# Bi_Dir_Circuit.net
KiCad netlist of a schematic drawn in Altium Designer
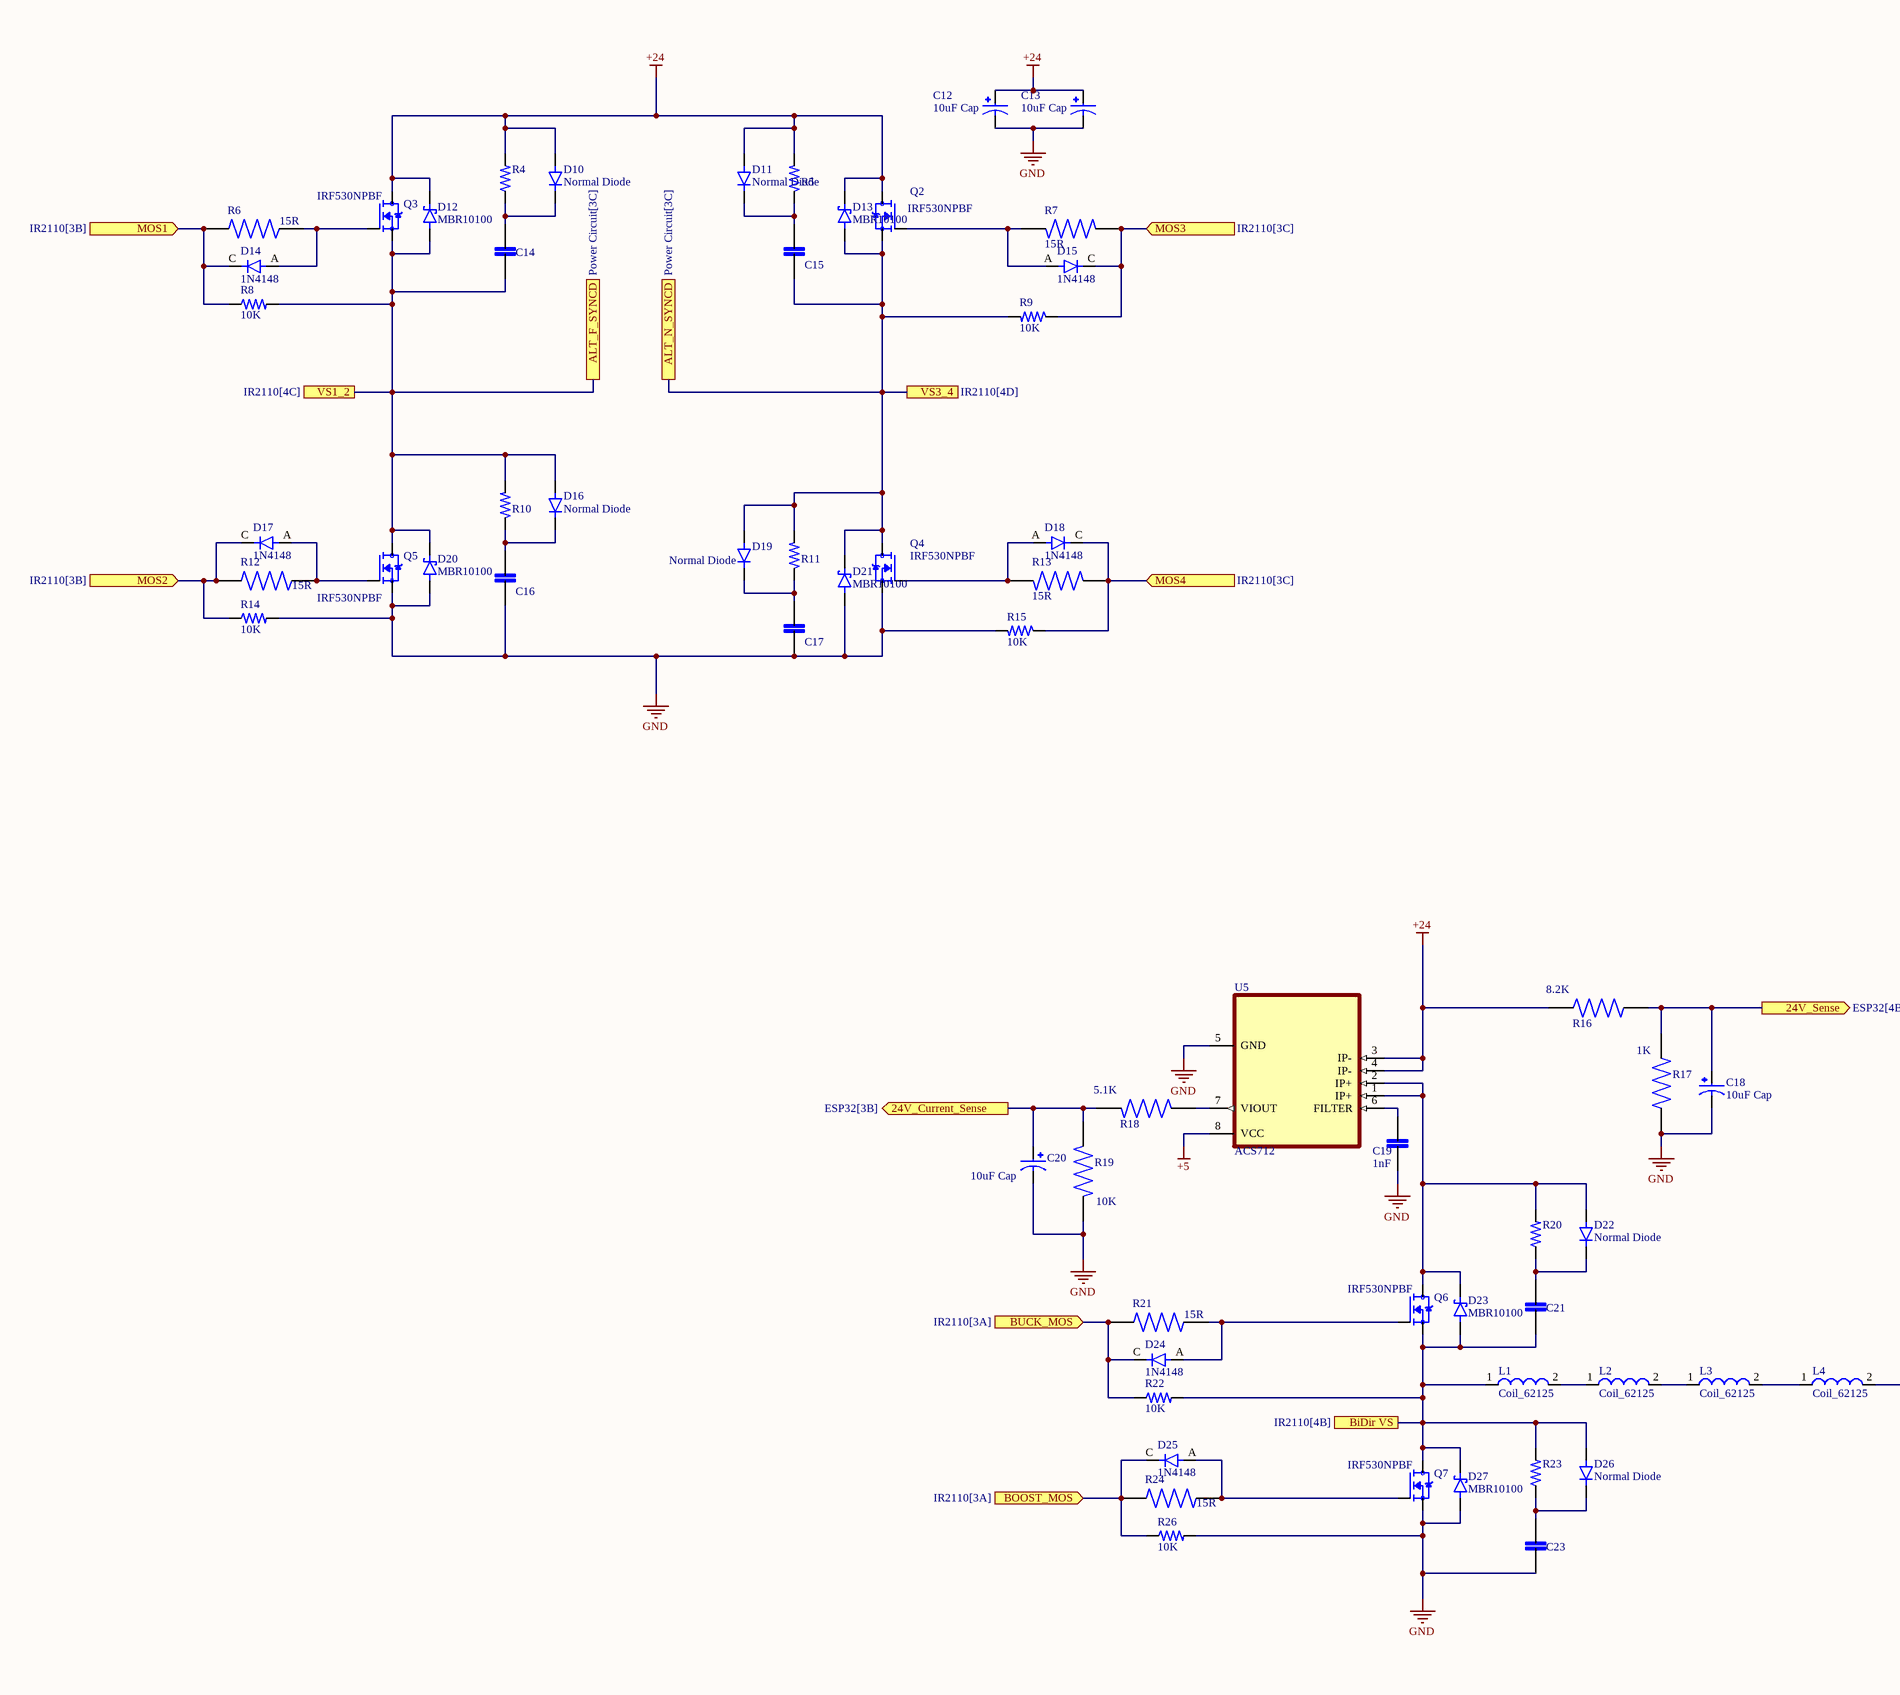
[diagram p0: Bi_Dir_Circuit.SchDoc, left]
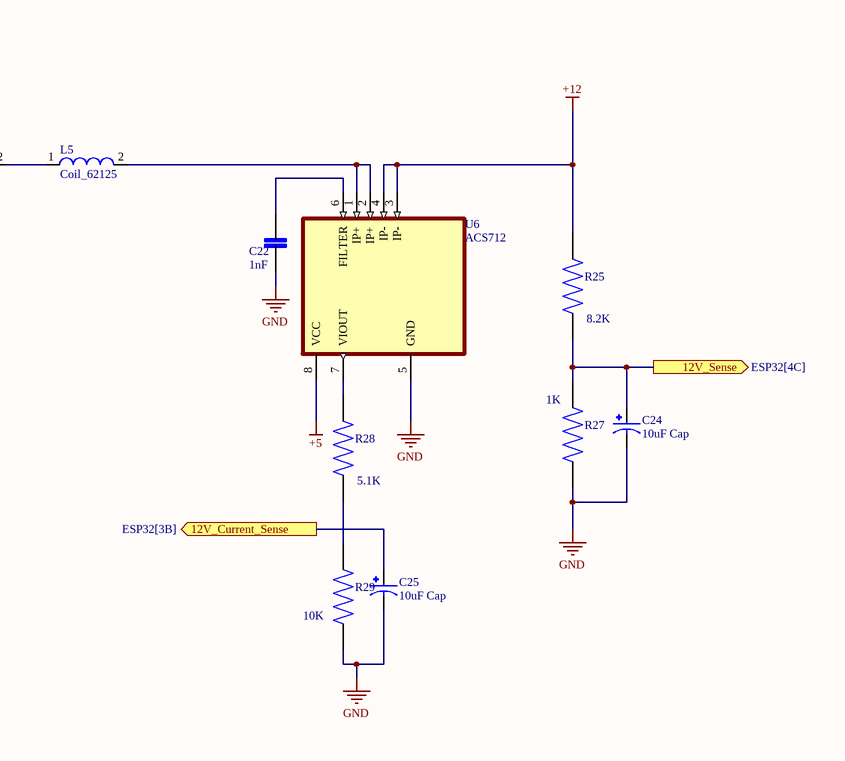
[diagram p1: Bi_Dir_Circuit.SchDoc, right]

(export (version "E")
  (design (tool "Eeschema 10.0.6"))
  (components
    (comp (ref "C12")
      (value "10uF Cap")
      (footprint "2200uF_Cap")
      (description "CAP ALUM 10UF 20% 50V RADIAL")
      (fields (field (name "MP") "ECE-A1HN100UI") (field (name "MF") "Panasonic"))
      (libsource (lib "MySCH_Library") (part "10uF Cap"))
    )
    (comp (ref "C13")
      (value "10uF Cap")
      (footprint "2200uF_Cap")
      (description "CAP ALUM 10UF 20% 50V RADIAL")
      (fields (field (name "MP") "ECE-A1HN100UI") (field (name "MF") "Panasonic"))
      (libsource (lib "MySCH_Library") (part "10uF Cap"))
    )
    (comp (ref "C14")
      (value "Ceramic Capacitor")
      (footprint "Ceramic Capacitor")
      (fields (field (name "MP") "LD051A121KAB2A") (field (name "MF") "AVX"))
      (libsource (lib "") (part "Ceramic Capacitor_1"))
    )
    (comp (ref "C15")
      (value "Ceramic Capacitor")
      (footprint "Ceramic Capacitor")
      (fields (field (name "MP") "LD051A121KAB2A") (field (name "MF") "AVX"))
      (libsource (lib "Capacitors Through Hole") (part "Ceramic Capacitor"))
    )
    (comp (ref "C16")
      (value "Ceramic Capacitor")
      (footprint "Ceramic Capacitor")
      (fields (field (name "MP") "LD051A121KAB2A") (field (name "MF") "AVX"))
      (libsource (lib "Capacitors Through Hole") (part "Ceramic Capacitor"))
    )
    (comp (ref "C17")
      (value "Ceramic Capacitor")
      (footprint "Ceramic Capacitor")
      (fields (field (name "MP") "LD051A121KAB2A") (field (name "MF") "AVX"))
      (libsource (lib "Capacitors Through Hole") (part "Ceramic Capacitor"))
    )
    (comp (ref "C18")
      (value "10uF Cap")
      (footprint "CAP_10uF")
      (description "CAP ALUM 10UF 20% 50V RADIAL")
      (fields (field (name "MP") "ECE-A1HN100UI") (field (name "MF") "Panasonic"))
      (libsource (lib "MySCH_Library") (part "10uF Cap"))
    )
    (comp (ref "C19")
      (value "1nF")
      (footprint "Ceramic Capacitor")
      (fields (field (name "MP") "LD051A121KAB2A") (field (name "MF") "AVX"))
      (libsource (lib "") (part "Ceramic Capacitor_1"))
    )
    (comp (ref "C20")
      (value "10uF Cap")
      (footprint "CAP_10uF")
      (description "CAP ALUM 10UF 20% 50V RADIAL")
      (fields (field (name "MP") "ECE-A1HN100UI") (field (name "MF") "Panasonic"))
      (libsource (lib "") (part "10uF Cap_1"))
    )
    (comp (ref "C21")
      (value "Ceramic Capacitor")
      (footprint "Ceramic Capacitor")
      (fields (field (name "MP") "LD051A121KAB2A") (field (name "MF") "AVX"))
      (libsource (lib "") (part "Ceramic Capacitor_1"))
    )
    (comp (ref "C22")
      (value "1nF")
      (footprint "Ceramic Capacitor")
      (fields (field (name "MP") "LD051A121KAB2A") (field (name "MF") "AVX"))
      (libsource (lib "") (part "Ceramic Capacitor_1"))
    )
    (comp (ref "C23")
      (value "Ceramic Capacitor")
      (footprint "Ceramic Capacitor")
      (fields (field (name "MP") "LD051A121KAB2A") (field (name "MF") "AVX"))
      (libsource (lib "") (part "Ceramic Capacitor_1"))
    )
    (comp (ref "C24")
      (value "10uF Cap")
      (footprint "CAP_10uF")
      (description "CAP ALUM 10UF 20% 50V RADIAL")
      (fields (field (name "MP") "ECE-A1HN100UI") (field (name "MF") "Panasonic"))
      (libsource (lib "MySCH_Library") (part "10uF Cap"))
    )
    (comp (ref "C25")
      (value "10uF Cap")
      (footprint "CAP_10uF")
      (description "CAP ALUM 10UF 20% 50V RADIAL")
      (fields (field (name "MP") "ECE-A1HN100UI") (field (name "MF") "Panasonic"))
      (libsource (lib "MySCH_Library") (part "10uF Cap"))
    )
    (comp (ref "D10")
      (value "Normal Diode")
      (footprint "Common Trhough Hole")
      (fields (field (name "MF") "NTE Electronics, Inc.") (field (name "MP") "1N4007"))
      (libsource (lib "Diodes Through Hole") (part "Normal Diode"))
    )
    (comp (ref "D11")
      (value "Normal Diode")
      (footprint "Common Trhough Hole")
      (fields (field (name "MF") "NTE Electronics, Inc.") (field (name "MP") "1N4007"))
      (libsource (lib "Diodes Through Hole") (part "Normal Diode"))
    )
    (comp (ref "D12")
      (value "MBR10100")
      (footprint "MBR10100")
      (fields (field (name "MF") "Diodes Inc.") (field (name "MP") "1N5817-T"))
      (libsource (lib "Diodes Through Hole") (part "MBR10100"))
    )
    (comp (ref "D13")
      (value "MBR10100")
      (footprint "MBR10100")
      (fields (field (name "MF") "Diodes Inc.") (field (name "MP") "1N5817-T"))
      (libsource (lib "Diodes Through Hole") (part "MBR10100"))
    )
    (comp (ref "D14")
      (value "1N4148")
      (footprint "1N4007 DIODE")
      (description "Diode Standard 1000 V 1A Through Hole DO-41")
      (fields (field (name "MF") "NTE Electronics, Inc.") (field (name "MP") "1N4007"))
      (libsource (lib "MySCH_Library") (part "1N4007"))
    )
    (comp (ref "D15")
      (value "1N4148")
      (footprint "1N4007 DIODE")
      (description "Diode Standard 1000 V 1A Through Hole DO-41")
      (fields (field (name "MF") "NTE Electronics, Inc.") (field (name "MP") "1N4007"))
      (libsource (lib "MySCH_Library") (part "1N4007"))
    )
    (comp (ref "D16")
      (value "Normal Diode")
      (footprint "Common Trhough Hole")
      (fields (field (name "MF") "NTE Electronics, Inc.") (field (name "MP") "1N4007"))
      (libsource (lib "Diodes Through Hole") (part "Normal Diode"))
    )
    (comp (ref "D17")
      (value "1N4148")
      (footprint "1N4007 DIODE")
      (description "Diode Standard 1000 V 1A Through Hole DO-41")
      (fields (field (name "MF") "NTE Electronics, Inc.") (field (name "MP") "1N4007"))
      (libsource (lib "MySCH_Library") (part "1N4007"))
    )
    (comp (ref "D18")
      (value "1N4148")
      (footprint "1N4007 DIODE")
      (description "Diode Standard 1000 V 1A Through Hole DO-41")
      (fields (field (name "MF") "NTE Electronics, Inc.") (field (name "MP") "1N4007"))
      (libsource (lib "MySCH_Library") (part "1N4007"))
    )
    (comp (ref "D19")
      (value "Normal Diode")
      (footprint "Common Trhough Hole")
      (fields (field (name "MF") "NTE Electronics, Inc.") (field (name "MP") "1N4007"))
      (libsource (lib "Diodes Through Hole") (part "Normal Diode"))
    )
    (comp (ref "D20")
      (value "MBR10100")
      (footprint "MBR10100")
      (fields (field (name "MF") "Diodes Inc.") (field (name "MP") "1N5817-T"))
      (libsource (lib "Diodes Through Hole") (part "MBR10100"))
    )
    (comp (ref "D21")
      (value "MBR10100")
      (footprint "MBR10100")
      (fields (field (name "MF") "Diodes Inc.") (field (name "MP") "1N5817-T"))
      (libsource (lib "Diodes Through Hole") (part "MBR10100"))
    )
    (comp (ref "D22")
      (value "Normal Diode")
      (footprint "Common Trhough Hole")
      (fields (field (name "MF") "NTE Electronics, Inc.") (field (name "MP") "1N4007"))
      (libsource (lib "Diodes Through Hole") (part "Normal Diode"))
    )
    (comp (ref "D23")
      (value "MBR10100")
      (footprint "MBR10100")
      (fields (field (name "MF") "Diodes Inc.") (field (name "MP") "1N5817-T"))
      (libsource (lib "Diodes Through Hole") (part "MBR10100"))
    )
    (comp (ref "D24")
      (value "1N4148")
      (footprint "1N4007 DIODE")
      (description "Diode Standard 1000 V 1A Through Hole DO-41")
      (fields (field (name "MF") "NTE Electronics, Inc.") (field (name "MP") "1N4007"))
      (libsource (lib "MySCH_Library") (part "1N4007"))
    )
    (comp (ref "D25")
      (value "1N4148")
      (footprint "1N4007 DIODE")
      (description "Diode Standard 1000 V 1A Through Hole DO-41")
      (fields (field (name "MF") "NTE Electronics, Inc.") (field (name "MP") "1N4007"))
      (libsource (lib "MySCH_Library") (part "1N4007"))
    )
    (comp (ref "D26")
      (value "Normal Diode")
      (footprint "Common Trhough Hole")
      (fields (field (name "MF") "NTE Electronics, Inc.") (field (name "MP") "1N4007"))
      (libsource (lib "Diodes Through Hole") (part "Normal Diode"))
    )
    (comp (ref "D27")
      (value "MBR10100")
      (footprint "MBR10100")
      (fields (field (name "MF") "Diodes Inc.") (field (name "MP") "1N5817-T"))
      (libsource (lib "Diodes Through Hole") (part "MBR10100"))
    )
    (comp (ref "L1")
      (value "Coil_62125")
      (footprint "Coil 65125")
      (description "Inductor Power Wirewound 470uH 10% 1KHz 25Q-Factor Ferrite 210mA 3.3Ohm DCR T/R")
      (fields (field (name "DIGI-KEY_PART_NUMBER") "SDR0604-471KLCT-ND") (field (name "MF") "Bourns"))
      (libsource (lib "MySCH_Library") (part "Coil_62125"))
    )
    (comp (ref "L2")
      (value "Coil_62125")
      (footprint "Coil 65125")
      (description "Inductor Power Wirewound 470uH 10% 1KHz 25Q-Factor Ferrite 210mA 3.3Ohm DCR T/R")
      (fields (field (name "DIGI-KEY_PART_NUMBER") "SDR0604-471KLCT-ND") (field (name "MF") "Bourns"))
      (libsource (lib "MySCH_Library") (part "Coil_62125"))
    )
    (comp (ref "L3")
      (value "Coil_62125")
      (footprint "Coil 65125")
      (description "Inductor Power Wirewound 470uH 10% 1KHz 25Q-Factor Ferrite 210mA 3.3Ohm DCR T/R")
      (fields (field (name "DIGI-KEY_PART_NUMBER") "SDR0604-471KLCT-ND") (field (name "MF") "Bourns"))
      (libsource (lib "MySCH_Library") (part "Coil_62125"))
    )
    (comp (ref "L4")
      (value "Coil_62125")
      (footprint "Coil 65125")
      (description "Inductor Power Wirewound 470uH 10% 1KHz 25Q-Factor Ferrite 210mA 3.3Ohm DCR T/R")
      (fields (field (name "DIGI-KEY_PART_NUMBER") "SDR0604-471KLCT-ND") (field (name "MF") "Bourns"))
      (libsource (lib "MySCH_Library") (part "Coil_62125"))
    )
    (comp (ref "L5")
      (value "Coil_62125")
      (footprint "Coil 65125")
      (description "Inductor Power Wirewound 470uH 10% 1KHz 25Q-Factor Ferrite 210mA 3.3Ohm DCR T/R")
      (fields (field (name "DIGI-KEY_PART_NUMBER") "SDR0604-471KLCT-ND") (field (name "MF") "Bourns"))
      (libsource (lib "MySCH_Library") (part "Coil_62125"))
    )
    (comp (ref "Q2")
      (value "IRF530NPBF")
      (footprint "IRF530N")
      (fields (field (name "MF") "Infineon Technologies"))
      (libsource (lib "MySCH_Library") (part "IRF530NPBF"))
    )
    (comp (ref "Q3")
      (value "IRF530NPBF")
      (footprint "IRF530N")
      (fields (field (name "MF") "Infineon Technologies"))
      (libsource (lib "MySCH_Library") (part "IRF530NPBF"))
    )
    (comp (ref "Q4")
      (value "IRF530NPBF")
      (footprint "IRF530N")
      (fields (field (name "MF") "Infineon Technologies"))
      (libsource (lib "MySCH_Library") (part "IRF530NPBF"))
    )
    (comp (ref "Q5")
      (value "IRF530NPBF")
      (footprint "IRF530N")
      (fields (field (name "MF") "Infineon Technologies"))
      (libsource (lib "MySCH_Library") (part "IRF530NPBF"))
    )
    (comp (ref "Q6")
      (value "IRF530NPBF")
      (footprint "IRF530N")
      (fields (field (name "MF") "Infineon Technologies"))
      (libsource (lib "MySCH_Library") (part "IRF530NPBF"))
    )
    (comp (ref "Q7")
      (value "IRF530NPBF")
      (footprint "IRF530N")
      (fields (field (name "MF") "Infineon Technologies"))
      (libsource (lib "MySCH_Library") (part "IRF530NPBF"))
    )
    (comp (ref "R4")
      (value "Resistor")
      (footprint "Resistor_Through Hole")
      (fields
        (field (name "MP") "2-2176053-0")
        (field (name "TOLERANCE") "1%")
        (field (name "MF") "TE Connectivity")
      )
      (libsource (lib "Resistors Through Hole") (part "Resistor"))
    )
    (comp (ref "R5")
      (value "Resistor")
      (footprint "Resistor_Through Hole")
      (fields
        (field (name "MP") "2-2176053-0")
        (field (name "TOLERANCE") "1%")
        (field (name "MF") "TE Connectivity")
      )
      (libsource (lib "Resistors Through Hole") (part "Resistor"))
    )
    (comp (ref "R6")
      (value "15R")
      (footprint "Resistor_Through Hole")
      (description "1.02 Ohms Â±1% 0.25W, 1/4W Through Hole Resistor Axial Metal Film")
      (fields (field (name "MP") "MFR-25FTE52-1R") (field (name "MF") "Yageo"))
      (libsource (lib "MySCH_Library") (part "Resistor_Through Hole"))
    )
    (comp (ref "R7")
      (value "15R")
      (footprint "Resistor_Through Hole")
      (description "1.02 Ohms Â±1% 0.25W, 1/4W Through Hole Resistor Axial Metal Film")
      (fields (field (name "MP") "MFR-25FTE52-1R") (field (name "MF") "Yageo"))
      (libsource (lib "MySCH_Library") (part "Resistor_Through Hole"))
    )
    (comp (ref "R8")
      (value "10K")
      (footprint "Resistor_Through Hole")
      (fields
        (field (name "MP") "2-2176053-0")
        (field (name "TOLERANCE") "1%")
        (field (name "MF") "TE Connectivity")
      )
      (libsource (lib "Resistors Through Hole") (part "Resistor"))
    )
    (comp (ref "R9")
      (value "10K")
      (footprint "Resistor_Through Hole")
      (fields
        (field (name "MP") "2-2176053-0")
        (field (name "TOLERANCE") "1%")
        (field (name "MF") "TE Connectivity")
      )
      (libsource (lib "Resistors Through Hole") (part "Resistor"))
    )
    (comp (ref "R10")
      (value "Resistor")
      (footprint "Resistor_Through Hole")
      (fields
        (field (name "MP") "2-2176053-0")
        (field (name "TOLERANCE") "1%")
        (field (name "MF") "TE Connectivity")
      )
      (libsource (lib "Resistors Through Hole") (part "Resistor"))
    )
    (comp (ref "R11")
      (value "Resistor")
      (footprint "Resistor_Through Hole")
      (fields
        (field (name "MP") "2-2176053-0")
        (field (name "TOLERANCE") "1%")
        (field (name "MF") "TE Connectivity")
      )
      (libsource (lib "Resistors Through Hole") (part "Resistor"))
    )
    (comp (ref "R12")
      (value "15R")
      (footprint "Resistor_Through Hole")
      (description "1.02 Ohms Â±1% 0.25W, 1/4W Through Hole Resistor Axial Metal Film")
      (fields (field (name "MP") "MFR-25FTE52-1R") (field (name "MF") "Yageo"))
      (libsource (lib "MySCH_Library") (part "Resistor_Through Hole"))
    )
    (comp (ref "R13")
      (value "15R")
      (footprint "Resistor_Through Hole")
      (description "1.02 Ohms Â±1% 0.25W, 1/4W Through Hole Resistor Axial Metal Film")
      (fields (field (name "MP") "MFR-25FTE52-1R") (field (name "MF") "Yageo"))
      (libsource (lib "MySCH_Library") (part "Resistor_Through Hole"))
    )
    (comp (ref "R14")
      (value "10K")
      (footprint "Resistor_Through Hole")
      (fields
        (field (name "MP") "2-2176053-0")
        (field (name "TOLERANCE") "1%")
        (field (name "MF") "TE Connectivity")
      )
      (libsource (lib "Resistors Through Hole") (part "Resistor"))
    )
    (comp (ref "R15")
      (value "10K")
      (footprint "Resistor_Through Hole")
      (fields
        (field (name "MP") "2-2176053-0")
        (field (name "TOLERANCE") "1%")
        (field (name "MF") "TE Connectivity")
      )
      (libsource (lib "Resistors Through Hole") (part "Resistor"))
    )
    (comp (ref "R16")
      (value "8.2K")
      (footprint "Resistor_Through Hole")
      (description "1.02 Ohms Â±1% 0.25W, 1/4W Through Hole Resistor Axial Metal Film")
      (fields (field (name "MP") "MFR-25FTE52-1R") (field (name "MF") "Yageo"))
      (libsource (lib "MySCH_Library") (part "Resistor_Through Hole"))
    )
    (comp (ref "R17")
      (value "1K")
      (footprint "Resistor_Through Hole")
      (description "1.02 Ohms Â±1% 0.25W, 1/4W Through Hole Resistor Axial Metal Film")
      (fields (field (name "MP") "MFR-25FTE52-1R") (field (name "MF") "Yageo"))
      (libsource (lib "MySCH_Library") (part "Resistor_Through Hole"))
    )
    (comp (ref "R18")
      (value "5.1K")
      (footprint "Resistor_Through Hole")
      (description "1.02 Ohms Â±1% 0.25W, 1/4W Through Hole Resistor Axial Metal Film")
      (fields (field (name "MP") "MFR-25FTE52-1R") (field (name "MF") "Yageo"))
      (libsource (lib "MySCH_Library") (part "Resistor_Through Hole"))
    )
    (comp (ref "R19")
      (value "10K")
      (footprint "Resistor_Through Hole")
      (description "1.02 Ohms Â±1% 0.25W, 1/4W Through Hole Resistor Axial Metal Film")
      (fields (field (name "MP") "MFR-25FTE52-1R") (field (name "MF") "Yageo"))
      (libsource (lib "MySCH_Library") (part "Resistor_Through Hole"))
    )
    (comp (ref "R20")
      (value "Resistor")
      (footprint "Resistor_Through Hole")
      (fields
        (field (name "MP") "2-2176053-0")
        (field (name "TOLERANCE") "1%")
        (field (name "MF") "TE Connectivity")
      )
      (libsource (lib "Resistors Through Hole") (part "Resistor"))
    )
    (comp (ref "R21")
      (value "15R")
      (footprint "Resistor_Through Hole")
      (description "1.02 Ohms Â±1% 0.25W, 1/4W Through Hole Resistor Axial Metal Film")
      (fields (field (name "MP") "MFR-25FTE52-1R") (field (name "MF") "Yageo"))
      (libsource (lib "MySCH_Library") (part "Resistor_Through Hole"))
    )
    (comp (ref "R22")
      (value "10K")
      (footprint "Resistor_Through Hole")
      (fields
        (field (name "MP") "2-2176053-0")
        (field (name "TOLERANCE") "1%")
        (field (name "MF") "TE Connectivity")
      )
      (libsource (lib "Resistors Through Hole") (part "Resistor"))
    )
    (comp (ref "R23")
      (value "Resistor")
      (footprint "Resistor_Through Hole")
      (fields
        (field (name "MP") "2-2176053-0")
        (field (name "TOLERANCE") "1%")
        (field (name "MF") "TE Connectivity")
      )
      (libsource (lib "Resistors Through Hole") (part "Resistor"))
    )
    (comp (ref "R24")
      (value "15R")
      (footprint "Resistor_Through Hole")
      (description "1.02 Ohms Â±1% 0.25W, 1/4W Through Hole Resistor Axial Metal Film")
      (fields (field (name "MP") "MFR-25FTE52-1R") (field (name "MF") "Yageo"))
      (libsource (lib "MySCH_Library") (part "Resistor_Through Hole"))
    )
    (comp (ref "R25")
      (value "8.2K")
      (footprint "Resistor_Through Hole")
      (description "1.02 Ohms Â±1% 0.25W, 1/4W Through Hole Resistor Axial Metal Film")
      (fields (field (name "MP") "MFR-25FTE52-1R") (field (name "MF") "Yageo"))
      (libsource (lib "MySCH_Library") (part "Resistor_Through Hole"))
    )
    (comp (ref "R26")
      (value "10K")
      (footprint "Resistor_Through Hole")
      (fields
        (field (name "MP") "2-2176053-0")
        (field (name "TOLERANCE") "1%")
        (field (name "MF") "TE Connectivity")
      )
      (libsource (lib "Resistors Through Hole") (part "Resistor"))
    )
    (comp (ref "R27")
      (value "1K")
      (footprint "Resistor_Through Hole")
      (description "1.02 Ohms Â±1% 0.25W, 1/4W Through Hole Resistor Axial Metal Film")
      (fields (field (name "MP") "MFR-25FTE52-1R") (field (name "MF") "Yageo"))
      (libsource (lib "MySCH_Library") (part "Resistor_Through Hole"))
    )
    (comp (ref "R28")
      (value "5.1K")
      (footprint "Resistor_Through Hole")
      (description "1.02 Ohms Â±1% 0.25W, 1/4W Through Hole Resistor Axial Metal Film")
      (fields (field (name "MP") "MFR-25FTE52-1R") (field (name "MF") "Yageo"))
      (libsource (lib "MySCH_Library") (part "Resistor_Through Hole"))
    )
    (comp (ref "R29")
      (value "10K")
      (footprint "Resistor_Through Hole")
      (description "1.02 Ohms Â±1% 0.25W, 1/4W Through Hole Resistor Axial Metal Film")
      (fields (field (name "MP") "MFR-25FTE52-1R") (field (name "MF") "Yageo"))
      (libsource (lib "MySCH_Library") (part "Resistor_Through Hole"))
    )
    (comp (ref "U5")
      (value "ACS712")
      (footprint "ACS712")
      (description "Current Sensor 5A 1 Channel Hall Effect, Open Loop Bidirectional 8-SOIC (0.154, 3.90mm Width)")
      (fields (field (name "MP") "ACS712ELCTR-05B-T") (field (name "MF") "Allegro MicroSystems LLC"))
      (libsource (lib "Hall Current Sensor") (part "ACS712"))
    )
    (comp (ref "U6")
      (value "ACS712")
      (footprint "ACS712")
      (description "Current Sensor 5A 1 Channel Hall Effect, Open Loop Bidirectional 8-SOIC (0.154, 3.90mm Width)")
      (fields (field (name "MP") "ACS712ELCTR-05B-T") (field (name "MF") "Allegro MicroSystems LLC"))
      (libsource (lib "Hall Current Sensor") (part "ACS712"))
    )
  )
  (nets
    (net (code "1") (name "+5") (class "Default")
      (node (ref "U5") (pin "8") (pinfunction "VCC_8") (pintype "power_in"))
      (node (ref "U6") (pin "8") (pinfunction "VCC_8") (pintype "power_in"))
    )
    (net (code "2") (name "+12") (class "Default")
      (node (ref "R25") (pin "2") (pinfunction "2_2") (pintype "passive"))
      (node (ref "U6") (pin "3") (pinfunction "IP-_3") (pintype "input"))
      (node (ref "U6") (pin "4") (pinfunction "IP-_4") (pintype "input"))
    )
    (net (code "3") (name "+24") (class "Default")
      (node (ref "C12") (pin "P") (pinfunction "P_P") (pintype "passive"))
      (node (ref "C13") (pin "P") (pinfunction "P_P") (pintype "passive"))
      (node (ref "D10") (pin "2") (pinfunction "A_2") (pintype "passive"))
      (node (ref "D11") (pin "2") (pinfunction "A_2") (pintype "passive"))
      (node (ref "D12") (pin "1") (pinfunction "K_1") (pintype "passive"))
      (node (ref "D13") (pin "1") (pinfunction "K_1") (pintype "passive"))
      (node (ref "Q2") (pin "2") (pinfunction "D_2") (pintype "passive"))
      (node (ref "Q3") (pin "2") (pinfunction "D_2") (pintype "passive"))
      (node (ref "R16") (pin "1") (pinfunction "1_1") (pintype "passive"))
      (node (ref "R4") (pin "2") (pinfunction "2_2") (pintype "passive"))
      (node (ref "R5") (pin "2") (pinfunction "2_2") (pintype "passive"))
      (node (ref "U5") (pin "3") (pinfunction "IP-_3") (pintype "input"))
      (node (ref "U5") (pin "4") (pinfunction "IP-_4") (pintype "input"))
    )
    (net (code "4") (name "/12V_Current_Sense") (class "Default")
      (node (ref "C25") (pin "P") (pinfunction "P_P") (pintype "passive"))
    )
    (net (code "5") (name "/12V_Sense") (class "Default")
      (node (ref "C24") (pin "P") (pinfunction "P_P") (pintype "passive"))
      (node (ref "R25") (pin "1") (pinfunction "1_1") (pintype "passive"))
      (node (ref "R27") (pin "2") (pinfunction "2_2") (pintype "passive"))
    )
    (net (code "6") (name "/24V_Current_Sense") (class "Default")
      (node (ref "C20") (pin "P") (pinfunction "P_P") (pintype "passive"))
      (node (ref "R18") (pin "1") (pinfunction "1_1") (pintype "passive"))
      (node (ref "R19") (pin "2") (pinfunction "2_2") (pintype "passive"))
    )
    (net (code "7") (name "/24V_Sense") (class "Default")
      (node (ref "C18") (pin "P") (pinfunction "P_P") (pintype "passive"))
      (node (ref "R16") (pin "2") (pinfunction "2_2") (pintype "passive"))
      (node (ref "R17") (pin "2") (pinfunction "2_2") (pintype "passive"))
    )
    (net (code "8") (name "/ALT_F_SYNCD") (class "Default")
      (node (ref "C14") (pin "1") (pinfunction "1_1") (pintype "passive"))
      (node (ref "D12") (pin "3") (pinfunction "A_3") (pintype "passive"))
      (node (ref "D16") (pin "2") (pinfunction "A_2") (pintype "passive"))
      (node (ref "D20") (pin "1") (pinfunction "K_1") (pintype "passive"))
      (node (ref "Q3") (pin "3") (pinfunction "S_3") (pintype "passive"))
      (node (ref "Q5") (pin "2") (pinfunction "D_2") (pintype "passive"))
      (node (ref "R10") (pin "2") (pinfunction "2_2") (pintype "passive"))
      (node (ref "R8") (pin "2") (pinfunction "2_2") (pintype "passive"))
    )
    (net (code "9") (name "/ALT_N_SYNCD") (class "Default")
      (node (ref "C15") (pin "1") (pinfunction "1_1") (pintype "passive"))
      (node (ref "D13") (pin "3") (pinfunction "A_3") (pintype "passive"))
      (node (ref "D19") (pin "2") (pinfunction "A_2") (pintype "passive"))
      (node (ref "D21") (pin "1") (pinfunction "K_1") (pintype "passive"))
      (node (ref "Q2") (pin "3") (pinfunction "S_3") (pintype "passive"))
      (node (ref "Q4") (pin "2") (pinfunction "D_2") (pintype "passive"))
      (node (ref "R11") (pin "2") (pinfunction "2_2") (pintype "passive"))
      (node (ref "R9") (pin "2") (pinfunction "2_2") (pintype "passive"))
    )
    (net (code "10") (name "/BOOST_MOS") (class "Default")
      (node (ref "D25") (pin "C") (pinfunction "C_C") (pintype "passive"))
      (node (ref "R24") (pin "1") (pinfunction "1_1") (pintype "passive"))
      (node (ref "R26") (pin "1") (pinfunction "1_1") (pintype "passive"))
    )
    (net (code "11") (name "/BUCK_MOS") (class "Default")
      (node (ref "D24") (pin "C") (pinfunction "C_C") (pintype "passive"))
      (node (ref "R21") (pin "1") (pinfunction "1_1") (pintype "passive"))
      (node (ref "R22") (pin "1") (pinfunction "1_1") (pintype "passive"))
    )
    (net (code "12") (name "/BiDir VS") (class "Default")
      (node (ref "C21") (pin "1") (pinfunction "1_1") (pintype "passive"))
      (node (ref "D23") (pin "3") (pinfunction "A_3") (pintype "passive"))
      (node (ref "D26") (pin "2") (pinfunction "A_2") (pintype "passive"))
      (node (ref "D27") (pin "1") (pinfunction "K_1") (pintype "passive"))
      (node (ref "L1") (pin "1") (pinfunction "1_1") (pintype "passive"))
      (node (ref "Q6") (pin "3") (pinfunction "S_3") (pintype "passive"))
      (node (ref "Q7") (pin "2") (pinfunction "D_2") (pintype "passive"))
      (node (ref "R22") (pin "2") (pinfunction "2_2") (pintype "passive"))
      (node (ref "R23") (pin "2") (pinfunction "2_2") (pintype "passive"))
    )
    (net (code "13") (name "/MOS1") (class "Default")
      (node (ref "D14") (pin "C") (pinfunction "C_C") (pintype "passive"))
      (node (ref "R6") (pin "1") (pinfunction "1_1") (pintype "passive"))
      (node (ref "R8") (pin "1") (pinfunction "1_1") (pintype "passive"))
    )
    (net (code "14") (name "/MOS2") (class "Default")
      (node (ref "D17") (pin "C") (pinfunction "C_C") (pintype "passive"))
      (node (ref "R12") (pin "1") (pinfunction "1_1") (pintype "passive"))
      (node (ref "R14") (pin "1") (pinfunction "1_1") (pintype "passive"))
    )
    (net (code "15") (name "/MOS3") (class "Default")
      (node (ref "D15") (pin "C") (pinfunction "C_C") (pintype "passive"))
      (node (ref "R7") (pin "1") (pinfunction "1_1") (pintype "passive"))
      (node (ref "R9") (pin "1") (pinfunction "1_1") (pintype "passive"))
    )
    (net (code "16") (name "/MOS4") (class "Default")
      (node (ref "D18") (pin "C") (pinfunction "C_C") (pintype "passive"))
      (node (ref "R13") (pin "1") (pinfunction "1_1") (pintype "passive"))
      (node (ref "R15") (pin "1") (pinfunction "1_1") (pintype "passive"))
    )
    (net (code "17") (name "GND") (class "Default")
      (node (ref "C12") (pin "N") (pinfunction "N_N") (pintype "passive"))
      (node (ref "C13") (pin "N") (pinfunction "N_N") (pintype "passive"))
      (node (ref "C16") (pin "1") (pinfunction "1_1") (pintype "passive"))
      (node (ref "C17") (pin "1") (pinfunction "1_1") (pintype "passive"))
      (node (ref "C18") (pin "N") (pinfunction "N_N") (pintype "passive"))
      (node (ref "C19") (pin "1") (pinfunction "1_1") (pintype "passive"))
      (node (ref "C20") (pin "N") (pinfunction "N_N") (pintype "passive"))
      (node (ref "C22") (pin "1") (pinfunction "1_1") (pintype "passive"))
      (node (ref "C23") (pin "1") (pinfunction "1_1") (pintype "passive"))
      (node (ref "C24") (pin "N") (pinfunction "N_N") (pintype "passive"))
      (node (ref "C25") (pin "N") (pinfunction "N_N") (pintype "passive"))
      (node (ref "D20") (pin "3") (pinfunction "A_3") (pintype "passive"))
      (node (ref "D21") (pin "3") (pinfunction "A_3") (pintype "passive"))
      (node (ref "D27") (pin "3") (pinfunction "A_3") (pintype "passive"))
      (node (ref "Q4") (pin "3") (pinfunction "S_3") (pintype "passive"))
      (node (ref "Q5") (pin "3") (pinfunction "S_3") (pintype "passive"))
      (node (ref "Q7") (pin "3") (pinfunction "S_3") (pintype "passive"))
      (node (ref "R14") (pin "2") (pinfunction "2_2") (pintype "passive"))
      (node (ref "R15") (pin "2") (pinfunction "2_2") (pintype "passive"))
      (node (ref "R17") (pin "1") (pinfunction "1_1") (pintype "passive"))
      (node (ref "R19") (pin "1") (pinfunction "1_1") (pintype "passive"))
      (node (ref "R26") (pin "2") (pinfunction "2_2") (pintype "passive"))
      (node (ref "R27") (pin "1") (pinfunction "1_1") (pintype "passive"))
      (node (ref "R29") (pin "1") (pinfunction "1_1") (pintype "passive"))
      (node (ref "U5") (pin "5") (pinfunction "GND_5") (pintype "power_in"))
      (node (ref "U6") (pin "5") (pinfunction "GND_5") (pintype "power_in"))
    )
    (net (code "18") (name "Net-(D10-K)") (class "Default")
      (node (ref "C14") (pin "2") (pinfunction "2_2") (pintype "passive"))
      (node (ref "D10") (pin "1") (pinfunction "K_1") (pintype "passive"))
      (node (ref "R4") (pin "1") (pinfunction "1_1") (pintype "passive"))
    )
    (net (code "19") (name "Net-(D11-K)") (class "Default")
      (node (ref "C15") (pin "2") (pinfunction "2_2") (pintype "passive"))
      (node (ref "D11") (pin "1") (pinfunction "K_1") (pintype "passive"))
      (node (ref "R5") (pin "1") (pinfunction "1_1") (pintype "passive"))
    )
    (net (code "20") (name "Net-(D16-K)") (class "Default")
      (node (ref "C16") (pin "2") (pinfunction "2_2") (pintype "passive"))
      (node (ref "D16") (pin "1") (pinfunction "K_1") (pintype "passive"))
      (node (ref "R10") (pin "1") (pinfunction "1_1") (pintype "passive"))
    )
    (net (code "21") (name "Net-(D19-K)") (class "Default")
      (node (ref "C17") (pin "2") (pinfunction "2_2") (pintype "passive"))
      (node (ref "D19") (pin "1") (pinfunction "K_1") (pintype "passive"))
      (node (ref "R11") (pin "1") (pinfunction "1_1") (pintype "passive"))
    )
    (net (code "22") (name "Net-(D22-A)") (class "Default")
      (node (ref "D22") (pin "2") (pinfunction "A_2") (pintype "passive"))
      (node (ref "D23") (pin "1") (pinfunction "K_1") (pintype "passive"))
      (node (ref "Q6") (pin "2") (pinfunction "D_2") (pintype "passive"))
      (node (ref "R20") (pin "2") (pinfunction "2_2") (pintype "passive"))
      (node (ref "U5") (pin "1") (pinfunction "IP+_1") (pintype "input"))
      (node (ref "U5") (pin "2") (pinfunction "IP+_2") (pintype "input"))
    )
    (net (code "23") (name "Net-(D22-K)") (class "Default")
      (node (ref "C21") (pin "2") (pinfunction "2_2") (pintype "passive"))
      (node (ref "D22") (pin "1") (pinfunction "K_1") (pintype "passive"))
      (node (ref "R20") (pin "1") (pinfunction "1_1") (pintype "passive"))
    )
    (net (code "24") (name "Net-(D26-K)") (class "Default")
      (node (ref "C23") (pin "2") (pinfunction "2_2") (pintype "passive"))
      (node (ref "D26") (pin "1") (pinfunction "K_1") (pintype "passive"))
      (node (ref "R23") (pin "1") (pinfunction "1_1") (pintype "passive"))
    )
    (net (code "25") (name "Net-(L1-Pad2)") (class "Default")
      (node (ref "L1") (pin "2") (pinfunction "2_2") (pintype "passive"))
      (node (ref "L2") (pin "1") (pinfunction "1_1") (pintype "passive"))
    )
    (net (code "26") (name "Net-(L2-Pad2)") (class "Default")
      (node (ref "L2") (pin "2") (pinfunction "2_2") (pintype "passive"))
      (node (ref "L3") (pin "1") (pinfunction "1_1") (pintype "passive"))
    )
    (net (code "27") (name "Net-(L3-Pad2)") (class "Default")
      (node (ref "L3") (pin "2") (pinfunction "2_2") (pintype "passive"))
      (node (ref "L4") (pin "1") (pinfunction "1_1") (pintype "passive"))
    )
    (net (code "28") (name "Net-(L4-Pad2)") (class "Default")
      (node (ref "L4") (pin "2") (pinfunction "2_2") (pintype "passive"))
      (node (ref "L5") (pin "1") (pinfunction "1_1") (pintype "passive"))
    )
    (net (code "29") (name "Net-(L5-Pad2)") (class "Default")
      (node (ref "L5") (pin "2") (pinfunction "2_2") (pintype "passive"))
      (node (ref "U6") (pin "1") (pinfunction "IP+_1") (pintype "input"))
      (node (ref "U6") (pin "2") (pinfunction "IP+_2") (pintype "input"))
    )
    (net (code "30") (name "Net-(Q2-G)") (class "Default")
      (node (ref "D15") (pin "A") (pinfunction "A_A") (pintype "passive"))
      (node (ref "Q2") (pin "1") (pinfunction "G_1") (pintype "passive"))
      (node (ref "R7") (pin "2") (pinfunction "2_2") (pintype "passive"))
    )
    (net (code "31") (name "Net-(Q3-G)") (class "Default")
      (node (ref "D14") (pin "A") (pinfunction "A_A") (pintype "passive"))
      (node (ref "Q3") (pin "1") (pinfunction "G_1") (pintype "passive"))
      (node (ref "R6") (pin "2") (pinfunction "2_2") (pintype "passive"))
    )
    (net (code "32") (name "Net-(Q4-G)") (class "Default")
      (node (ref "D18") (pin "A") (pinfunction "A_A") (pintype "passive"))
      (node (ref "Q4") (pin "1") (pinfunction "G_1") (pintype "passive"))
      (node (ref "R13") (pin "2") (pinfunction "2_2") (pintype "passive"))
    )
    (net (code "33") (name "Net-(Q5-G)") (class "Default")
      (node (ref "D17") (pin "A") (pinfunction "A_A") (pintype "passive"))
      (node (ref "Q5") (pin "1") (pinfunction "G_1") (pintype "passive"))
      (node (ref "R12") (pin "2") (pinfunction "2_2") (pintype "passive"))
    )
    (net (code "34") (name "Net-(Q6-G)") (class "Default")
      (node (ref "D24") (pin "A") (pinfunction "A_A") (pintype "passive"))
      (node (ref "Q6") (pin "1") (pinfunction "G_1") (pintype "passive"))
      (node (ref "R21") (pin "2") (pinfunction "2_2") (pintype "passive"))
    )
    (net (code "35") (name "Net-(Q7-G)") (class "Default")
      (node (ref "D25") (pin "A") (pinfunction "A_A") (pintype "passive"))
      (node (ref "Q7") (pin "1") (pinfunction "G_1") (pintype "passive"))
      (node (ref "R24") (pin "2") (pinfunction "2_2") (pintype "passive"))
    )
    (net (code "36") (name "Net-(R28-Pad1)") (class "Default")
      (node (ref "R28") (pin "1") (pinfunction "1_1") (pintype "passive"))
      (node (ref "R29") (pin "2") (pinfunction "2_2") (pintype "passive"))
    )
    (net (code "37") (name "Net-(U5-FILTER)") (class "Default")
      (node (ref "C19") (pin "2") (pinfunction "2_2") (pintype "passive"))
      (node (ref "U5") (pin "6") (pinfunction "FILTER_6") (pintype "input"))
    )
    (net (code "38") (name "Net-(U5-VIOUT)") (class "Default")
      (node (ref "R18") (pin "2") (pinfunction "2_2") (pintype "passive"))
      (node (ref "U5") (pin "7") (pinfunction "VIOUT_7") (pintype "output"))
    )
    (net (code "39") (name "Net-(U6-FILTER)") (class "Default")
      (node (ref "C22") (pin "2") (pinfunction "2_2") (pintype "passive"))
      (node (ref "U6") (pin "6") (pinfunction "FILTER_6") (pintype "input"))
    )
    (net (code "40") (name "Net-(U6-VIOUT)") (class "Default")
      (node (ref "R28") (pin "2") (pinfunction "2_2") (pintype "passive"))
      (node (ref "U6") (pin "7") (pinfunction "VIOUT_7") (pintype "output"))
    )
  )
)
